# tick-ref-gps-disp.net
KiCad netlist of a schematic drawn in EAGLE
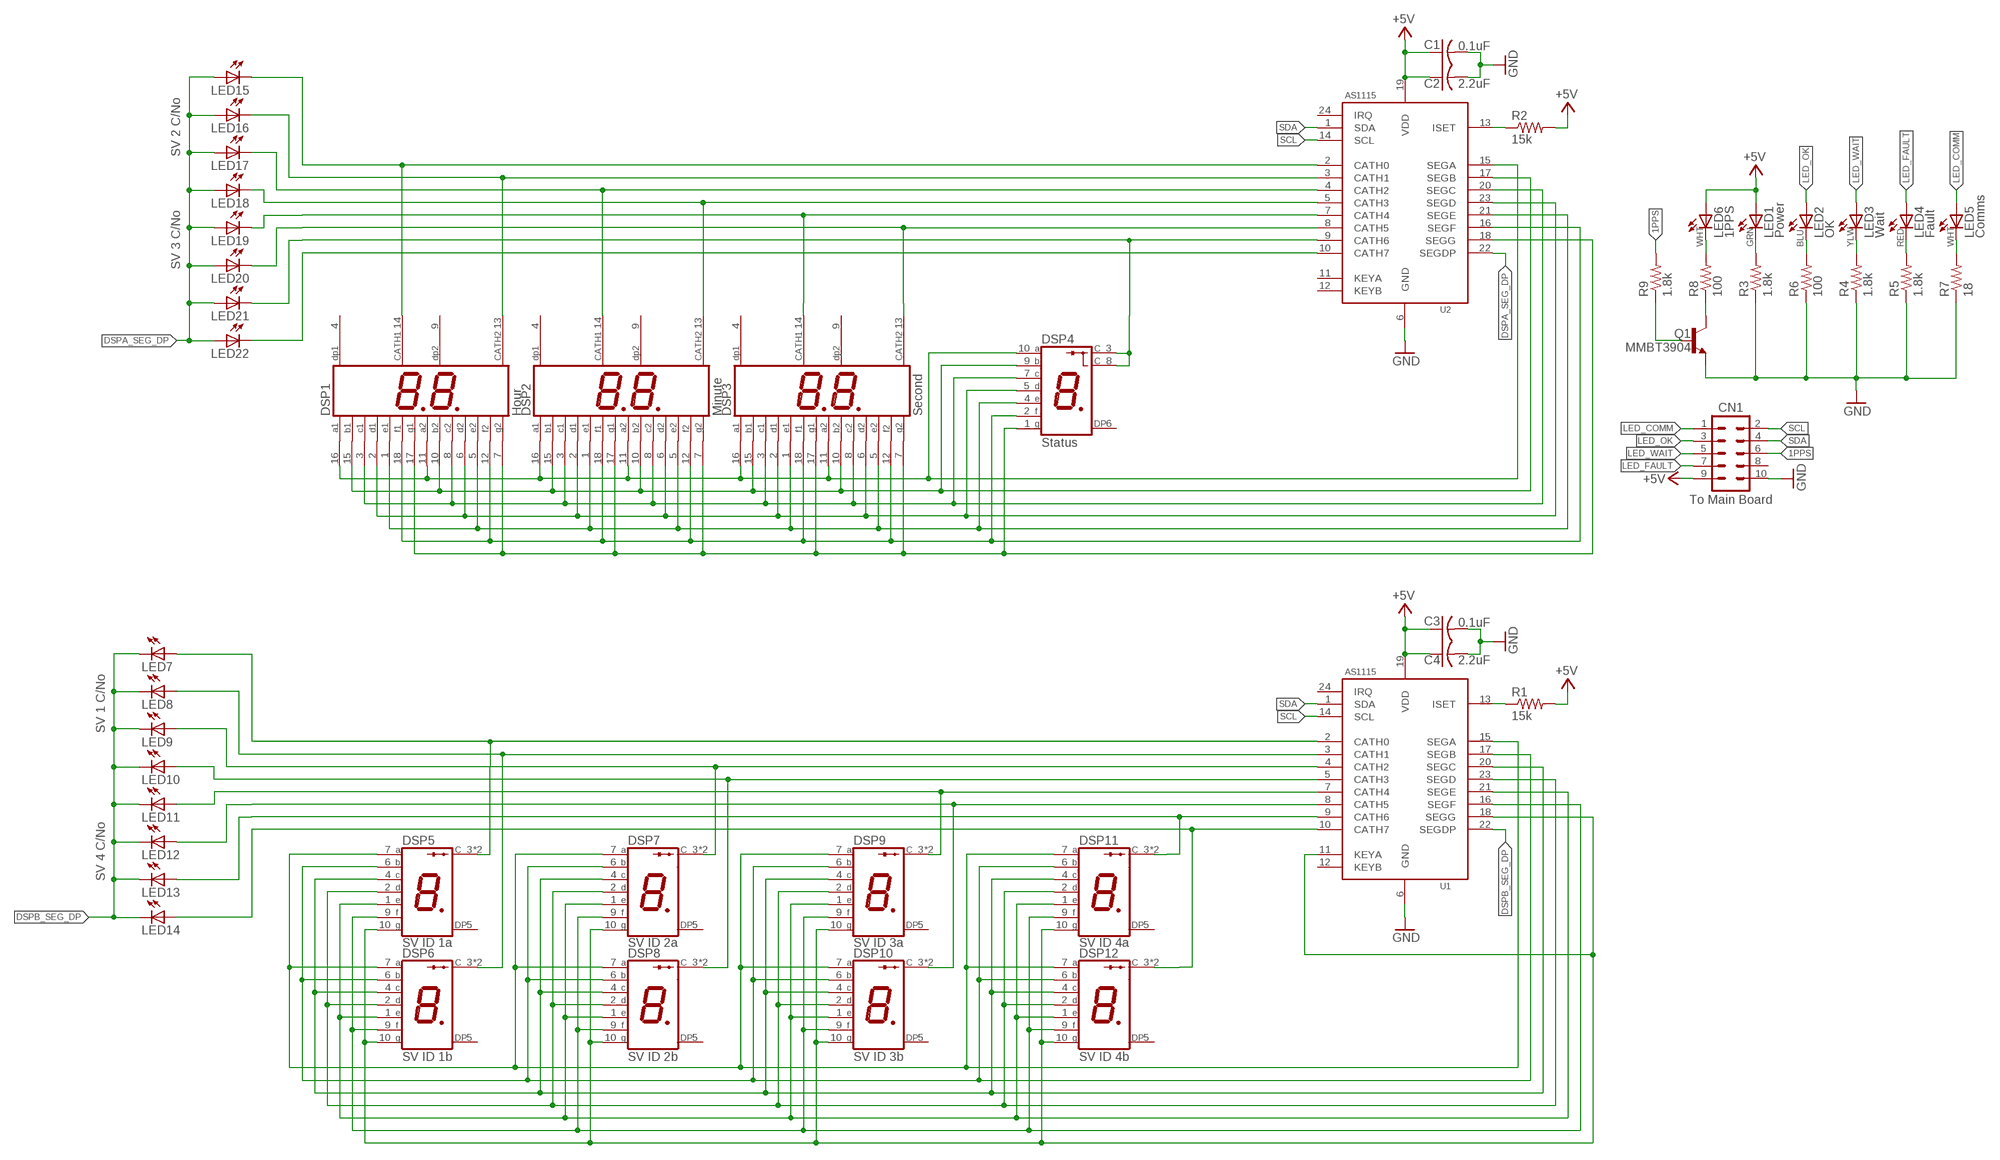
[diagram p0: schematic, sheet 1]

(export (version "E")
  (design (tool "Eeschema 10.0.6"))
  (components
    (comp (ref "C1")
      (value "0.1uF")
      (footprint "eagle-import:C0603")
      (libsource (lib "eagle-import") (part "C-USC0603"))
    )
    (comp (ref "C2")
      (value "2.2uF")
      (footprint "eagle-import:C0805")
      (libsource (lib "eagle-import") (part "C-USC0805"))
    )
    (comp (ref "C3")
      (value "0.1uF")
      (footprint "eagle-import:C0603")
      (libsource (lib "eagle-import") (part "C-USC0603"))
    )
    (comp (ref "C4")
      (value "2.2uF")
      (footprint "eagle-import:C0805")
      (libsource (lib "eagle-import") (part "C-USC0805"))
    )
    (comp (ref "CN1")
      (value "To Main Board")
      (footprint "eagle-import:AVR_ICSP")
      (libsource (lib "eagle-import") (part "M05X2PTH"))
    )
    (comp (ref "DSP1")
      (value "Hour")
      (footprint "eagle-import:LUMEX-LDD-C81XRI")
      (libsource (lib "eagle-import") (part "LUMEX-LDD-C81XRI"))
    )
    (comp (ref "DSP2")
      (value "Minute")
      (footprint "eagle-import:LUMEX-LDD-C81XRI")
      (libsource (lib "eagle-import") (part "LUMEX-LDD-C81XRI"))
    )
    (comp (ref "DSP3")
      (value "Second")
      (footprint "eagle-import:LUMEX-LDD-C81XRI")
      (libsource (lib "eagle-import") (part "LUMEX-LDD-C81XRI"))
    )
    (comp (ref "DSP4")
      (value "Status")
      (footprint "eagle-import:S4301B")
      (libsource (lib "eagle-import") (part "S4301B"))
    )
    (comp (ref "DSP5")
      (value "SV ID 1a")
      (footprint "eagle-import:KINGBRIGHT-ACSA02")
      (libsource (lib "eagle-import") (part "KINGBRIGHT-ACSC02"))
    )
    (comp (ref "DSP6")
      (value "SV ID 1b")
      (footprint "eagle-import:KINGBRIGHT-ACSA02")
      (libsource (lib "eagle-import") (part "KINGBRIGHT-ACSC02"))
    )
    (comp (ref "DSP7")
      (value "SV ID 2a")
      (footprint "eagle-import:KINGBRIGHT-ACSA02")
      (libsource (lib "eagle-import") (part "KINGBRIGHT-ACSC02"))
    )
    (comp (ref "DSP8")
      (value "SV ID 2b")
      (footprint "eagle-import:KINGBRIGHT-ACSA02")
      (libsource (lib "eagle-import") (part "KINGBRIGHT-ACSC02"))
    )
    (comp (ref "DSP9")
      (value "SV ID 3a")
      (footprint "eagle-import:KINGBRIGHT-ACSA02")
      (libsource (lib "eagle-import") (part "KINGBRIGHT-ACSC02"))
    )
    (comp (ref "DSP10")
      (value "SV ID 3b")
      (footprint "eagle-import:KINGBRIGHT-ACSA02")
      (libsource (lib "eagle-import") (part "KINGBRIGHT-ACSC02"))
    )
    (comp (ref "DSP11")
      (value "SV ID 4a")
      (footprint "eagle-import:KINGBRIGHT-ACSA02")
      (libsource (lib "eagle-import") (part "KINGBRIGHT-ACSC02"))
    )
    (comp (ref "DSP12")
      (value "SV ID 4b")
      (footprint "eagle-import:KINGBRIGHT-ACSA02")
      (libsource (lib "eagle-import") (part "KINGBRIGHT-ACSC02"))
    )
    (comp (ref "LED1")
      (value "Power")
      (footprint "eagle-import:LED5MM")
      (libsource (lib "eagle-import") (part "LED5MM"))
    )
    (comp (ref "LED2")
      (value "OK")
      (footprint "eagle-import:LED5MM")
      (libsource (lib "eagle-import") (part "LED5MM"))
    )
    (comp (ref "LED3")
      (value "Wait")
      (footprint "eagle-import:LED5MM")
      (libsource (lib "eagle-import") (part "LED5MM"))
    )
    (comp (ref "LED4")
      (value "Fault")
      (footprint "eagle-import:LED5MM")
      (libsource (lib "eagle-import") (part "LED5MM"))
    )
    (comp (ref "LED5")
      (value "Comms")
      (footprint "eagle-import:LED5MM")
      (libsource (lib "eagle-import") (part "LED5MM"))
    )
    (comp (ref "LED6")
      (value "1PPS")
      (footprint "eagle-import:LED5MM")
      (libsource (lib "eagle-import") (part "LED5MM"))
    )
    (comp (ref "LED7")
      (value "LEDCHIP-LED0805")
      (footprint "eagle-import:CHIP-LED0805")
      (libsource (lib "eagle-import") (part "LEDCHIP-LED0805"))
    )
    (comp (ref "LED8")
      (value "LEDCHIP-LED0805")
      (footprint "eagle-import:CHIP-LED0805")
      (libsource (lib "eagle-import") (part "LEDCHIP-LED0805"))
    )
    (comp (ref "LED9")
      (value "LEDCHIP-LED0805")
      (footprint "eagle-import:CHIP-LED0805")
      (libsource (lib "eagle-import") (part "LEDCHIP-LED0805"))
    )
    (comp (ref "LED10")
      (value "LEDCHIP-LED0805")
      (footprint "eagle-import:CHIP-LED0805")
      (libsource (lib "eagle-import") (part "LEDCHIP-LED0805"))
    )
    (comp (ref "LED11")
      (value "LEDCHIP-LED0805")
      (footprint "eagle-import:CHIP-LED0805")
      (libsource (lib "eagle-import") (part "LEDCHIP-LED0805"))
    )
    (comp (ref "LED12")
      (value "LEDCHIP-LED0805")
      (footprint "eagle-import:CHIP-LED0805")
      (libsource (lib "eagle-import") (part "LEDCHIP-LED0805"))
    )
    (comp (ref "LED13")
      (value "LEDCHIP-LED0805")
      (footprint "eagle-import:CHIP-LED0805")
      (libsource (lib "eagle-import") (part "LEDCHIP-LED0805"))
    )
    (comp (ref "LED14")
      (value "LEDCHIP-LED0805")
      (footprint "eagle-import:CHIP-LED0805")
      (libsource (lib "eagle-import") (part "LEDCHIP-LED0805"))
    )
    (comp (ref "LED15")
      (value "LEDCHIP-LED0805")
      (footprint "eagle-import:CHIP-LED0805")
      (libsource (lib "eagle-import") (part "LEDCHIP-LED0805"))
    )
    (comp (ref "LED16")
      (value "LEDCHIP-LED0805")
      (footprint "eagle-import:CHIP-LED0805")
      (libsource (lib "eagle-import") (part "LEDCHIP-LED0805"))
    )
    (comp (ref "LED17")
      (value "LEDCHIP-LED0805")
      (footprint "eagle-import:CHIP-LED0805")
      (libsource (lib "eagle-import") (part "LEDCHIP-LED0805"))
    )
    (comp (ref "LED18")
      (value "LEDCHIP-LED0805")
      (footprint "eagle-import:CHIP-LED0805")
      (libsource (lib "eagle-import") (part "LEDCHIP-LED0805"))
    )
    (comp (ref "LED19")
      (value "LEDCHIP-LED0805")
      (footprint "eagle-import:CHIP-LED0805")
      (libsource (lib "eagle-import") (part "LEDCHIP-LED0805"))
    )
    (comp (ref "LED20")
      (value "LEDCHIP-LED0805")
      (footprint "eagle-import:CHIP-LED0805")
      (libsource (lib "eagle-import") (part "LEDCHIP-LED0805"))
    )
    (comp (ref "LED21")
      (value "LEDCHIP-LED0805")
      (footprint "eagle-import:CHIP-LED0805")
      (libsource (lib "eagle-import") (part "LEDCHIP-LED0805"))
    )
    (comp (ref "LED22")
      (value "LEDCHIP-LED0805")
      (footprint "eagle-import:CHIP-LED0805")
      (libsource (lib "eagle-import") (part "LEDCHIP-LED0805"))
    )
    (comp (ref "Q1")
      (value "MMBT3904")
      (footprint "eagle-import:SOT23")
      (libsource (lib "eagle-import") (part "TRANSISTOR_NPNSOT23"))
    )
    (comp (ref "R1")
      (value "15k")
      (footprint "eagle-import:R0603")
      (libsource (lib "eagle-import") (part "R-US_R0603"))
    )
    (comp (ref "R2")
      (value "15k")
      (footprint "eagle-import:R0603")
      (libsource (lib "eagle-import") (part "R-US_R0603"))
    )
    (comp (ref "R3")
      (value "1.8k")
      (footprint "eagle-import:R0603")
      (libsource (lib "eagle-import") (part "R-US_R0603"))
    )
    (comp (ref "R4")
      (value "1.8k")
      (footprint "eagle-import:R0603")
      (libsource (lib "eagle-import") (part "R-US_R0603"))
    )
    (comp (ref "R5")
      (value "1.8k")
      (footprint "eagle-import:R0603")
      (libsource (lib "eagle-import") (part "R-US_R0603"))
    )
    (comp (ref "R6")
      (value "100")
      (footprint "eagle-import:R0603")
      (libsource (lib "eagle-import") (part "R-US_R0603"))
    )
    (comp (ref "R7")
      (value "18")
      (footprint "eagle-import:R0603")
      (libsource (lib "eagle-import") (part "R-US_R0603"))
    )
    (comp (ref "R8")
      (value "100")
      (footprint "eagle-import:R0603")
      (libsource (lib "eagle-import") (part "R-US_R0603"))
    )
    (comp (ref "R9")
      (value "1.8k")
      (footprint "eagle-import:R0603")
      (libsource (lib "eagle-import") (part "R-US_R0603"))
    )
    (comp (ref "U1")
      (value "AS1115")
      (footprint "eagle-import:QSOP24")
      (libsource (lib "eagle-import") (part "AS1115"))
    )
    (comp (ref "U2")
      (value "AS1115")
      (footprint "eagle-import:QSOP24")
      (libsource (lib "eagle-import") (part "AS1115"))
    )
  )
  (nets
    (net (code "1") (name "+5V") (class "Default")
      (node (ref "C1") (pin "1") (pinfunction "1_1") (pintype "passive"))
      (node (ref "C2") (pin "1") (pinfunction "1_1") (pintype "passive"))
      (node (ref "C3") (pin "1") (pinfunction "1_1") (pintype "passive"))
      (node (ref "C4") (pin "1") (pinfunction "1_1") (pintype "passive"))
      (node (ref "CN1") (pin "9") (pinfunction "9_9") (pintype "passive"))
      (node (ref "LED1") (pin "A") (pinfunction "A_A") (pintype "passive"))
      (node (ref "LED6") (pin "A") (pinfunction "A_A") (pintype "passive"))
      (node (ref "R1") (pin "2") (pinfunction "2_2") (pintype "passive"))
      (node (ref "R2") (pin "2") (pinfunction "2_2") (pintype "passive"))
      (node (ref "U1") (pin "19") (pinfunction "VDD_19") (pintype "power_in"))
      (node (ref "U2") (pin "19") (pinfunction "VDD_19") (pintype "power_in"))
    )
    (net (code "2") (name "1PPS") (class "Default")
      (node (ref "CN1") (pin "6") (pinfunction "6_6") (pintype "passive"))
      (node (ref "R9") (pin "2") (pinfunction "2_2") (pintype "passive"))
    )
    (net (code "3") (name "DSPA_SEG_DP") (class "Default")
      (node (ref "LED15") (pin "A") (pinfunction "A_A") (pintype "passive"))
      (node (ref "LED16") (pin "A") (pinfunction "A_A") (pintype "passive"))
      (node (ref "LED17") (pin "A") (pinfunction "A_A") (pintype "passive"))
      (node (ref "LED18") (pin "A") (pinfunction "A_A") (pintype "passive"))
      (node (ref "LED19") (pin "A") (pinfunction "A_A") (pintype "passive"))
      (node (ref "LED20") (pin "A") (pinfunction "A_A") (pintype "passive"))
      (node (ref "LED21") (pin "A") (pinfunction "A_A") (pintype "passive"))
      (node (ref "LED22") (pin "A") (pinfunction "A_A") (pintype "passive"))
      (node (ref "U2") (pin "22") (pinfunction "SEGDP_22") (pintype "output"))
    )
    (net (code "4") (name "DSPB_SEG_DP") (class "Default")
      (node (ref "LED10") (pin "C") (pinfunction "C_C") (pintype "passive"))
      (node (ref "LED11") (pin "C") (pinfunction "C_C") (pintype "passive"))
      (node (ref "LED12") (pin "C") (pinfunction "C_C") (pintype "passive"))
      (node (ref "LED13") (pin "C") (pinfunction "C_C") (pintype "passive"))
      (node (ref "LED14") (pin "C") (pinfunction "C_C") (pintype "passive"))
      (node (ref "LED7") (pin "C") (pinfunction "C_C") (pintype "passive"))
      (node (ref "LED8") (pin "C") (pinfunction "C_C") (pintype "passive"))
      (node (ref "LED9") (pin "C") (pinfunction "C_C") (pintype "passive"))
      (node (ref "U1") (pin "22") (pinfunction "SEGDP_22") (pintype "output"))
    )
    (net (code "5") (name "GND") (class "Default")
      (node (ref "C1") (pin "2") (pinfunction "2_2") (pintype "passive"))
      (node (ref "C2") (pin "2") (pinfunction "2_2") (pintype "passive"))
      (node (ref "C3") (pin "2") (pinfunction "2_2") (pintype "passive"))
      (node (ref "C4") (pin "2") (pinfunction "2_2") (pintype "passive"))
      (node (ref "CN1") (pin "10") (pinfunction "10_10") (pintype "passive"))
      (node (ref "Q1") (pin "2") (pinfunction "E_2") (pintype "passive"))
      (node (ref "R3") (pin "1") (pinfunction "1_1") (pintype "passive"))
      (node (ref "R4") (pin "1") (pinfunction "1_1") (pintype "passive"))
      (node (ref "R5") (pin "1") (pinfunction "1_1") (pintype "passive"))
      (node (ref "R6") (pin "1") (pinfunction "1_1") (pintype "passive"))
      (node (ref "R7") (pin "1") (pinfunction "1_1") (pintype "passive"))
      (node (ref "U1") (pin "6") (pinfunction "GND_6") (pintype "power_in"))
      (node (ref "U2") (pin "6") (pinfunction "GND_6") (pintype "power_in"))
    )
    (net (code "6") (name "LED_COMM") (class "Default")
      (node (ref "CN1") (pin "1") (pinfunction "1_1") (pintype "passive"))
      (node (ref "LED5") (pin "A") (pinfunction "A_A") (pintype "passive"))
    )
    (net (code "7") (name "LED_FAULT") (class "Default")
      (node (ref "CN1") (pin "7") (pinfunction "7_7") (pintype "passive"))
      (node (ref "LED4") (pin "A") (pinfunction "A_A") (pintype "passive"))
    )
    (net (code "8") (name "LED_OK") (class "Default")
      (node (ref "CN1") (pin "3") (pinfunction "3_3") (pintype "passive"))
      (node (ref "LED2") (pin "A") (pinfunction "A_A") (pintype "passive"))
    )
    (net (code "9") (name "LED_WAIT") (class "Default")
      (node (ref "CN1") (pin "5") (pinfunction "5_5") (pintype "passive"))
      (node (ref "LED3") (pin "A") (pinfunction "A_A") (pintype "passive"))
    )
    (net (code "10") (name "Net-(DSP1-A1)") (class "Default")
      (node (ref "DSP1") (pin "11") (pinfunction "A2_11") (pintype "passive"))
      (node (ref "DSP1") (pin "16") (pinfunction "A1_16") (pintype "passive"))
      (node (ref "DSP2") (pin "11") (pinfunction "A2_11") (pintype "passive"))
      (node (ref "DSP2") (pin "16") (pinfunction "A1_16") (pintype "passive"))
      (node (ref "DSP3") (pin "11") (pinfunction "A2_11") (pintype "passive"))
      (node (ref "DSP3") (pin "16") (pinfunction "A1_16") (pintype "passive"))
      (node (ref "DSP4") (pin "10") (pinfunction "A_10") (pintype "passive"))
      (node (ref "U2") (pin "15") (pinfunction "SEGA_15") (pintype "output"))
    )
    (net (code "11") (name "Net-(DSP1-B1)") (class "Default")
      (node (ref "DSP1") (pin "10") (pinfunction "B2_10") (pintype "passive"))
      (node (ref "DSP1") (pin "15") (pinfunction "B1_15") (pintype "passive"))
      (node (ref "DSP2") (pin "10") (pinfunction "B2_10") (pintype "passive"))
      (node (ref "DSP2") (pin "15") (pinfunction "B1_15") (pintype "passive"))
      (node (ref "DSP3") (pin "10") (pinfunction "B2_10") (pintype "passive"))
      (node (ref "DSP3") (pin "15") (pinfunction "B1_15") (pintype "passive"))
      (node (ref "DSP4") (pin "9") (pinfunction "B_9") (pintype "passive"))
      (node (ref "U2") (pin "17") (pinfunction "SEGB_17") (pintype "output"))
    )
    (net (code "12") (name "Net-(DSP1-C1)") (class "Default")
      (node (ref "DSP1") (pin "3") (pinfunction "C1_3") (pintype "passive"))
      (node (ref "DSP1") (pin "8") (pinfunction "C2_8") (pintype "passive"))
      (node (ref "DSP2") (pin "3") (pinfunction "C1_3") (pintype "passive"))
      (node (ref "DSP2") (pin "8") (pinfunction "C2_8") (pintype "passive"))
      (node (ref "DSP3") (pin "3") (pinfunction "C1_3") (pintype "passive"))
      (node (ref "DSP3") (pin "8") (pinfunction "C2_8") (pintype "passive"))
      (node (ref "DSP4") (pin "7") (pinfunction "C_7") (pintype "passive"))
      (node (ref "U2") (pin "20") (pinfunction "SEGC_20") (pintype "output"))
    )
    (net (code "13") (name "Net-(DSP1-CATH1)") (class "Default")
      (node (ref "DSP1") (pin "14") (pinfunction "CATH1_14") (pintype "passive"))
      (node (ref "LED15") (pin "C") (pinfunction "C_C") (pintype "passive"))
      (node (ref "U2") (pin "2") (pinfunction "CATH0_2") (pintype "output"))
    )
    (net (code "14") (name "Net-(DSP1-CATH2)") (class "Default")
      (node (ref "DSP1") (pin "13") (pinfunction "CATH2_13") (pintype "passive"))
      (node (ref "LED16") (pin "C") (pinfunction "C_C") (pintype "passive"))
      (node (ref "U2") (pin "3") (pinfunction "CATH1_3") (pintype "output"))
    )
    (net (code "15") (name "Net-(DSP1-D1)") (class "Default")
      (node (ref "DSP1") (pin "2") (pinfunction "D1_2") (pintype "passive"))
      (node (ref "DSP1") (pin "6") (pinfunction "D2_6") (pintype "passive"))
      (node (ref "DSP2") (pin "2") (pinfunction "D1_2") (pintype "passive"))
      (node (ref "DSP2") (pin "6") (pinfunction "D2_6") (pintype "passive"))
      (node (ref "DSP3") (pin "2") (pinfunction "D1_2") (pintype "passive"))
      (node (ref "DSP3") (pin "6") (pinfunction "D2_6") (pintype "passive"))
      (node (ref "DSP4") (pin "5") (pinfunction "D_5") (pintype "passive"))
      (node (ref "U2") (pin "23") (pinfunction "SEGD_23") (pintype "output"))
    )
    (net (code "16") (name "Net-(DSP1-E1)") (class "Default")
      (node (ref "DSP1") (pin "1") (pinfunction "E1_1") (pintype "passive"))
      (node (ref "DSP1") (pin "5") (pinfunction "E2_5") (pintype "passive"))
      (node (ref "DSP2") (pin "1") (pinfunction "E1_1") (pintype "passive"))
      (node (ref "DSP2") (pin "5") (pinfunction "E2_5") (pintype "passive"))
      (node (ref "DSP3") (pin "1") (pinfunction "E1_1") (pintype "passive"))
      (node (ref "DSP3") (pin "5") (pinfunction "E2_5") (pintype "passive"))
      (node (ref "DSP4") (pin "4") (pinfunction "E_4") (pintype "passive"))
      (node (ref "U2") (pin "21") (pinfunction "SEGE_21") (pintype "output"))
    )
    (net (code "17") (name "Net-(DSP1-F1)") (class "Default")
      (node (ref "DSP1") (pin "12") (pinfunction "F2_12") (pintype "passive"))
      (node (ref "DSP1") (pin "18") (pinfunction "F1_18") (pintype "passive"))
      (node (ref "DSP2") (pin "12") (pinfunction "F2_12") (pintype "passive"))
      (node (ref "DSP2") (pin "18") (pinfunction "F1_18") (pintype "passive"))
      (node (ref "DSP3") (pin "12") (pinfunction "F2_12") (pintype "passive"))
      (node (ref "DSP3") (pin "18") (pinfunction "F1_18") (pintype "passive"))
      (node (ref "DSP4") (pin "2") (pinfunction "F_2") (pintype "passive"))
      (node (ref "U2") (pin "16") (pinfunction "SEGF_16") (pintype "output"))
    )
    (net (code "18") (name "Net-(DSP1-G1)") (class "Default")
      (node (ref "DSP1") (pin "17") (pinfunction "G1_17") (pintype "passive"))
      (node (ref "DSP1") (pin "7") (pinfunction "G2_7") (pintype "passive"))
      (node (ref "DSP2") (pin "17") (pinfunction "G1_17") (pintype "passive"))
      (node (ref "DSP2") (pin "7") (pinfunction "G2_7") (pintype "passive"))
      (node (ref "DSP3") (pin "17") (pinfunction "G1_17") (pintype "passive"))
      (node (ref "DSP3") (pin "7") (pinfunction "G2_7") (pintype "passive"))
      (node (ref "DSP4") (pin "1") (pinfunction "G_1") (pintype "passive"))
      (node (ref "U2") (pin "18") (pinfunction "SEGG_18") (pintype "output"))
    )
    (net (code "19") (name "Net-(DSP2-CATH1)") (class "Default")
      (node (ref "DSP2") (pin "14") (pinfunction "CATH1_14") (pintype "passive"))
      (node (ref "LED17") (pin "C") (pinfunction "C_C") (pintype "passive"))
      (node (ref "U2") (pin "4") (pinfunction "CATH2_4") (pintype "output"))
    )
    (net (code "20") (name "Net-(DSP2-CATH2)") (class "Default")
      (node (ref "DSP2") (pin "13") (pinfunction "CATH2_13") (pintype "passive"))
      (node (ref "LED18") (pin "C") (pinfunction "C_C") (pintype "passive"))
      (node (ref "U2") (pin "5") (pinfunction "CATH3_5") (pintype "output"))
    )
    (net (code "21") (name "Net-(DSP3-CATH1)") (class "Default")
      (node (ref "DSP3") (pin "14") (pinfunction "CATH1_14") (pintype "passive"))
      (node (ref "LED19") (pin "C") (pinfunction "C_C") (pintype "passive"))
      (node (ref "U2") (pin "7") (pinfunction "CATH4_7") (pintype "output"))
    )
    (net (code "22") (name "Net-(DSP3-CATH2)") (class "Default")
      (node (ref "DSP3") (pin "13") (pinfunction "CATH2_13") (pintype "passive"))
      (node (ref "LED20") (pin "C") (pinfunction "C_C") (pintype "passive"))
      (node (ref "U2") (pin "8") (pinfunction "CATH5_8") (pintype "output"))
    )
    (net (code "23") (name "Net-(DSP10-A)") (class "Default")
      (node (ref "DSP10") (pin "7") (pinfunction "A_7") (pintype "passive"))
      (node (ref "DSP11") (pin "7") (pinfunction "A_7") (pintype "passive"))
      (node (ref "DSP12") (pin "7") (pinfunction "A_7") (pintype "passive"))
      (node (ref "DSP5") (pin "7") (pinfunction "A_7") (pintype "passive"))
      (node (ref "DSP6") (pin "7") (pinfunction "A_7") (pintype "passive"))
      (node (ref "DSP7") (pin "7") (pinfunction "A_7") (pintype "passive"))
      (node (ref "DSP8") (pin "7") (pinfunction "A_7") (pintype "passive"))
      (node (ref "DSP9") (pin "7") (pinfunction "A_7") (pintype "passive"))
      (node (ref "U1") (pin "15") (pinfunction "SEGA_15") (pintype "output"))
    )
    (net (code "24") (name "Net-(DSP10-B)") (class "Default")
      (node (ref "DSP10") (pin "6") (pinfunction "B_6") (pintype "passive"))
      (node (ref "DSP11") (pin "6") (pinfunction "B_6") (pintype "passive"))
      (node (ref "DSP12") (pin "6") (pinfunction "B_6") (pintype "passive"))
      (node (ref "DSP5") (pin "6") (pinfunction "B_6") (pintype "passive"))
      (node (ref "DSP6") (pin "6") (pinfunction "B_6") (pintype "passive"))
      (node (ref "DSP7") (pin "6") (pinfunction "B_6") (pintype "passive"))
      (node (ref "DSP8") (pin "6") (pinfunction "B_6") (pintype "passive"))
      (node (ref "DSP9") (pin "6") (pinfunction "B_6") (pintype "passive"))
      (node (ref "U1") (pin "17") (pinfunction "SEGB_17") (pintype "output"))
    )
    (net (code "25") (name "Net-(DSP10-C)") (class "Default")
      (node (ref "DSP10") (pin "4") (pinfunction "C_4") (pintype "passive"))
      (node (ref "DSP11") (pin "4") (pinfunction "C_4") (pintype "passive"))
      (node (ref "DSP12") (pin "4") (pinfunction "C_4") (pintype "passive"))
      (node (ref "DSP5") (pin "4") (pinfunction "C_4") (pintype "passive"))
      (node (ref "DSP6") (pin "4") (pinfunction "C_4") (pintype "passive"))
      (node (ref "DSP7") (pin "4") (pinfunction "C_4") (pintype "passive"))
      (node (ref "DSP8") (pin "4") (pinfunction "C_4") (pintype "passive"))
      (node (ref "DSP9") (pin "4") (pinfunction "C_4") (pintype "passive"))
      (node (ref "U1") (pin "20") (pinfunction "SEGC_20") (pintype "output"))
    )
    (net (code "26") (name "Net-(DSP10-D)") (class "Default")
      (node (ref "DSP10") (pin "2") (pinfunction "D_2") (pintype "passive"))
      (node (ref "DSP11") (pin "2") (pinfunction "D_2") (pintype "passive"))
      (node (ref "DSP12") (pin "2") (pinfunction "D_2") (pintype "passive"))
      (node (ref "DSP5") (pin "2") (pinfunction "D_2") (pintype "passive"))
      (node (ref "DSP6") (pin "2") (pinfunction "D_2") (pintype "passive"))
      (node (ref "DSP7") (pin "2") (pinfunction "D_2") (pintype "passive"))
      (node (ref "DSP8") (pin "2") (pinfunction "D_2") (pintype "passive"))
      (node (ref "DSP9") (pin "2") (pinfunction "D_2") (pintype "passive"))
      (node (ref "U1") (pin "23") (pinfunction "SEGD_23") (pintype "output"))
    )
    (net (code "27") (name "Net-(DSP10-E)") (class "Default")
      (node (ref "DSP10") (pin "1") (pinfunction "E_1") (pintype "passive"))
      (node (ref "DSP11") (pin "1") (pinfunction "E_1") (pintype "passive"))
      (node (ref "DSP12") (pin "1") (pinfunction "E_1") (pintype "passive"))
      (node (ref "DSP5") (pin "1") (pinfunction "E_1") (pintype "passive"))
      (node (ref "DSP6") (pin "1") (pinfunction "E_1") (pintype "passive"))
      (node (ref "DSP7") (pin "1") (pinfunction "E_1") (pintype "passive"))
      (node (ref "DSP8") (pin "1") (pinfunction "E_1") (pintype "passive"))
      (node (ref "DSP9") (pin "1") (pinfunction "E_1") (pintype "passive"))
      (node (ref "U1") (pin "21") (pinfunction "SEGE_21") (pintype "output"))
    )
    (net (code "28") (name "Net-(DSP10-F)") (class "Default")
      (node (ref "DSP10") (pin "9") (pinfunction "F_9") (pintype "passive"))
      (node (ref "DSP11") (pin "9") (pinfunction "F_9") (pintype "passive"))
      (node (ref "DSP12") (pin "9") (pinfunction "F_9") (pintype "passive"))
      (node (ref "DSP5") (pin "9") (pinfunction "F_9") (pintype "passive"))
      (node (ref "DSP6") (pin "9") (pinfunction "F_9") (pintype "passive"))
      (node (ref "DSP7") (pin "9") (pinfunction "F_9") (pintype "passive"))
      (node (ref "DSP8") (pin "9") (pinfunction "F_9") (pintype "passive"))
      (node (ref "DSP9") (pin "9") (pinfunction "F_9") (pintype "passive"))
      (node (ref "U1") (pin "16") (pinfunction "SEGF_16") (pintype "output"))
    )
    (net (code "29") (name "Net-(DSP10-G)") (class "Default")
      (node (ref "DSP10") (pin "10") (pinfunction "G_10") (pintype "passive"))
      (node (ref "DSP11") (pin "10") (pinfunction "G_10") (pintype "passive"))
      (node (ref "DSP12") (pin "10") (pinfunction "G_10") (pintype "passive"))
      (node (ref "DSP5") (pin "10") (pinfunction "G_10") (pintype "passive"))
      (node (ref "DSP6") (pin "10") (pinfunction "G_10") (pintype "passive"))
      (node (ref "DSP7") (pin "10") (pinfunction "G_10") (pintype "passive"))
      (node (ref "DSP8") (pin "10") (pinfunction "G_10") (pintype "passive"))
      (node (ref "DSP9") (pin "10") (pinfunction "G_10") (pintype "passive"))
      (node (ref "U1") (pin "11") (pinfunction "KEYA_11") (pintype "bidirectional"))
      (node (ref "U1") (pin "18") (pinfunction "SEGG_18") (pintype "output"))
    )
    (net (code "30") (name "Net-(LED1-C)") (class "Default")
      (node (ref "LED1") (pin "K") (pinfunction "C_K") (pintype "passive"))
      (node (ref "R3") (pin "2") (pinfunction "2_2") (pintype "passive"))
    )
    (net (code "31") (name "Net-(LED2-C)") (class "Default")
      (node (ref "LED2") (pin "K") (pinfunction "C_K") (pintype "passive"))
      (node (ref "R6") (pin "2") (pinfunction "2_2") (pintype "passive"))
    )
    (net (code "32") (name "Net-(LED3-C)") (class "Default")
      (node (ref "LED3") (pin "K") (pinfunction "C_K") (pintype "passive"))
      (node (ref "R4") (pin "2") (pinfunction "2_2") (pintype "passive"))
    )
    (net (code "33") (name "Net-(LED4-C)") (class "Default")
      (node (ref "LED4") (pin "K") (pinfunction "C_K") (pintype "passive"))
      (node (ref "R5") (pin "2") (pinfunction "2_2") (pintype "passive"))
    )
    (net (code "34") (name "Net-(LED5-C)") (class "Default")
      (node (ref "LED5") (pin "K") (pinfunction "C_K") (pintype "passive"))
      (node (ref "R7") (pin "2") (pinfunction "2_2") (pintype "passive"))
    )
    (net (code "35") (name "Net-(LED6-C)") (class "Default")
      (node (ref "LED6") (pin "K") (pinfunction "C_K") (pintype "passive"))
      (node (ref "R8") (pin "2") (pinfunction "2_2") (pintype "passive"))
    )
    (net (code "36") (name "Net-(Q1-B)") (class "Default")
      (node (ref "Q1") (pin "1") (pinfunction "B_1") (pintype "passive"))
      (node (ref "R9") (pin "1") (pinfunction "1_1") (pintype "passive"))
    )
    (net (code "37") (name "Net-(Q1-C)") (class "Default")
      (node (ref "Q1") (pin "3") (pinfunction "C_3") (pintype "passive"))
      (node (ref "R8") (pin "1") (pinfunction "1_1") (pintype "passive"))
    )
    (net (code "38") (name "Net-(U1-CATH0)") (class "Default")
      (node (ref "DSP5") (pin "3") (pinfunction "CATH_3") (pintype "passive"))
      (node (ref "DSP5") (pin "8") (pinfunction "CATH_8") (pintype "passive"))
      (node (ref "LED7") (pin "A") (pinfunction "A_A") (pintype "passive"))
      (node (ref "U1") (pin "2") (pinfunction "CATH0_2") (pintype "output"))
    )
    (net (code "39") (name "Net-(U1-CATH1)") (class "Default")
      (node (ref "DSP6") (pin "3") (pinfunction "CATH_3") (pintype "passive"))
      (node (ref "DSP6") (pin "8") (pinfunction "CATH_8") (pintype "passive"))
      (node (ref "LED8") (pin "A") (pinfunction "A_A") (pintype "passive"))
      (node (ref "U1") (pin "3") (pinfunction "CATH1_3") (pintype "output"))
    )
    (net (code "40") (name "Net-(U1-CATH2)") (class "Default")
      (node (ref "DSP7") (pin "3") (pinfunction "CATH_3") (pintype "passive"))
      (node (ref "DSP7") (pin "8") (pinfunction "CATH_8") (pintype "passive"))
      (node (ref "LED9") (pin "A") (pinfunction "A_A") (pintype "passive"))
      (node (ref "U1") (pin "4") (pinfunction "CATH2_4") (pintype "output"))
    )
    (net (code "41") (name "Net-(U1-CATH3)") (class "Default")
      (node (ref "DSP8") (pin "3") (pinfunction "CATH_3") (pintype "passive"))
      (node (ref "DSP8") (pin "8") (pinfunction "CATH_8") (pintype "passive"))
      (node (ref "LED10") (pin "A") (pinfunction "A_A") (pintype "passive"))
      (node (ref "U1") (pin "5") (pinfunction "CATH3_5") (pintype "output"))
    )
    (net (code "42") (name "Net-(U1-CATH4)") (class "Default")
      (node (ref "DSP9") (pin "3") (pinfunction "CATH_3") (pintype "passive"))
      (node (ref "DSP9") (pin "8") (pinfunction "CATH_8") (pintype "passive"))
      (node (ref "LED11") (pin "A") (pinfunction "A_A") (pintype "passive"))
      (node (ref "U1") (pin "7") (pinfunction "CATH4_7") (pintype "output"))
    )
    (net (code "43") (name "Net-(U1-CATH5)") (class "Default")
      (node (ref "DSP10") (pin "3") (pinfunction "CATH_3") (pintype "passive"))
      (node (ref "DSP10") (pin "8") (pinfunction "CATH_8") (pintype "passive"))
      (node (ref "LED12") (pin "A") (pinfunction "A_A") (pintype "passive"))
      (node (ref "U1") (pin "8") (pinfunction "CATH5_8") (pintype "output"))
    )
    (net (code "44") (name "Net-(U1-CATH6)") (class "Default")
      (node (ref "DSP11") (pin "3") (pinfunction "CATH_3") (pintype "passive"))
      (node (ref "DSP11") (pin "8") (pinfunction "CATH_8") (pintype "passive"))
      (node (ref "LED13") (pin "A") (pinfunction "A_A") (pintype "passive"))
      (node (ref "U1") (pin "9") (pinfunction "CATH6_9") (pintype "output"))
    )
    (net (code "45") (name "Net-(U1-CATH7)") (class "Default")
      (node (ref "DSP12") (pin "3") (pinfunction "CATH_3") (pintype "passive"))
      (node (ref "DSP12") (pin "8") (pinfunction "CATH_8") (pintype "passive"))
      (node (ref "LED14") (pin "A") (pinfunction "A_A") (pintype "passive"))
      (node (ref "U1") (pin "10") (pinfunction "CATH7_10") (pintype "output"))
    )
    (net (code "46") (name "Net-(U1-ISET)") (class "Default")
      (node (ref "R1") (pin "1") (pinfunction "1_1") (pintype "passive"))
      (node (ref "U1") (pin "13") (pinfunction "ISET_13") (pintype "input"))
    )
    (net (code "47") (name "Net-(U2-CATH6)") (class "Default")
      (node (ref "DSP4") (pin "3") (pinfunction "C_3") (pintype "passive"))
      (node (ref "DSP4") (pin "8") (pinfunction "C_8") (pintype "passive"))
      (node (ref "LED21") (pin "C") (pinfunction "C_C") (pintype "passive"))
      (node (ref "U2") (pin "9") (pinfunction "CATH6_9") (pintype "output"))
    )
    (net (code "48") (name "Net-(U2-CATH7)") (class "Default")
      (node (ref "LED22") (pin "C") (pinfunction "C_C") (pintype "passive"))
      (node (ref "U2") (pin "10") (pinfunction "CATH7_10") (pintype "output"))
    )
    (net (code "49") (name "Net-(U2-ISET)") (class "Default")
      (node (ref "R2") (pin "1") (pinfunction "1_1") (pintype "passive"))
      (node (ref "U2") (pin "13") (pinfunction "ISET_13") (pintype "input"))
    )
    (net (code "50") (name "SCL") (class "Default")
      (node (ref "CN1") (pin "2") (pinfunction "2_2") (pintype "passive"))
      (node (ref "U1") (pin "14") (pinfunction "SCL_14") (pintype "bidirectional"))
      (node (ref "U2") (pin "14") (pinfunction "SCL_14") (pintype "bidirectional"))
    )
    (net (code "51") (name "SDA") (class "Default")
      (node (ref "CN1") (pin "4") (pinfunction "4_4") (pintype "passive"))
      (node (ref "U1") (pin "1") (pinfunction "SDA_1") (pintype "bidirectional"))
      (node (ref "U2") (pin "1") (pinfunction "SDA_1") (pintype "bidirectional"))
    )
    (net (code "52") (name "unconnected-(CN1-Pad8)") (class "Default")
      (node (ref "CN1") (pin "8") (pinfunction "8_8") (pintype "passive"))
    )
    (net (code "53") (name "unconnected-(DSP1-DP1-Pad4)") (class "Default")
      (node (ref "DSP1") (pin "4") (pinfunction "DP1_4") (pintype "passive"))
    )
    (net (code "54") (name "unconnected-(DSP1-DP2-Pad9)") (class "Default")
      (node (ref "DSP1") (pin "9") (pinfunction "DP2_9") (pintype "passive"))
    )
    (net (code "55") (name "unconnected-(DSP2-DP1-Pad4)") (class "Default")
      (node (ref "DSP2") (pin "4") (pinfunction "DP1_4") (pintype "passive"))
    )
    (net (code "56") (name "unconnected-(DSP2-DP2-Pad9)") (class "Default")
      (node (ref "DSP2") (pin "9") (pinfunction "DP2_9") (pintype "passive"))
    )
    (net (code "57") (name "unconnected-(DSP3-DP1-Pad4)") (class "Default")
      (node (ref "DSP3") (pin "4") (pinfunction "DP1_4") (pintype "passive"))
    )
    (net (code "58") (name "unconnected-(DSP3-DP2-Pad9)") (class "Default")
      (node (ref "DSP3") (pin "9") (pinfunction "DP2_9") (pintype "passive"))
    )
    (net (code "59") (name "unconnected-(DSP4-DP-Pad6)") (class "Default")
      (node (ref "DSP4") (pin "6") (pinfunction "DP_6") (pintype "passive"))
    )
    (net (code "60") (name "unconnected-(DSP5-DP-Pad5)") (class "Default")
      (node (ref "DSP5") (pin "5") (pinfunction "DP_5") (pintype "passive"))
    )
    (net (code "61") (name "unconnected-(DSP6-DP-Pad5)") (class "Default")
      (node (ref "DSP6") (pin "5") (pinfunction "DP_5") (pintype "passive"))
    )
    (net (code "62") (name "unconnected-(DSP7-DP-Pad5)") (class "Default")
      (node (ref "DSP7") (pin "5") (pinfunction "DP_5") (pintype "passive"))
    )
    (net (code "63") (name "unconnected-(DSP8-DP-Pad5)") (class "Default")
      (node (ref "DSP8") (pin "5") (pinfunction "DP_5") (pintype "passive"))
    )
    (net (code "64") (name "unconnected-(DSP9-DP-Pad5)") (class "Default")
      (node (ref "DSP9") (pin "5") (pinfunction "DP_5") (pintype "passive"))
    )
    (net (code "65") (name "unconnected-(DSP10-DP-Pad5)") (class "Default")
      (node (ref "DSP10") (pin "5") (pinfunction "DP_5") (pintype "passive"))
    )
    (net (code "66") (name "unconnected-(DSP11-DP-Pad5)") (class "Default")
      (node (ref "DSP11") (pin "5") (pinfunction "DP_5") (pintype "passive"))
    )
    (net (code "67") (name "unconnected-(DSP12-DP-Pad5)") (class "Default")
      (node (ref "DSP12") (pin "5") (pinfunction "DP_5") (pintype "passive"))
    )
    (net (code "68") (name "unconnected-(U1-IRQ-Pad24)") (class "Default")
      (node (ref "U1") (pin "24") (pinfunction "IRQ_24") (pintype "output"))
    )
    (net (code "69") (name "unconnected-(U1-KEYB-Pad12)") (class "Default")
      (node (ref "U1") (pin "12") (pinfunction "KEYB_12") (pintype "bidirectional"))
    )
    (net (code "70") (name "unconnected-(U2-IRQ-Pad24)") (class "Default")
      (node (ref "U2") (pin "24") (pinfunction "IRQ_24") (pintype "output"))
    )
    (net (code "71") (name "unconnected-(U2-KEYA-Pad11)") (class "Default")
      (node (ref "U2") (pin "11") (pinfunction "KEYA_11") (pintype "bidirectional"))
    )
    (net (code "72") (name "unconnected-(U2-KEYB-Pad12)") (class "Default")
      (node (ref "U2") (pin "12") (pinfunction "KEYB_12") (pintype "bidirectional"))
    )
  )
)
